# Qgo3.net
KiCad netlist of a schematic drawn in EAGLE
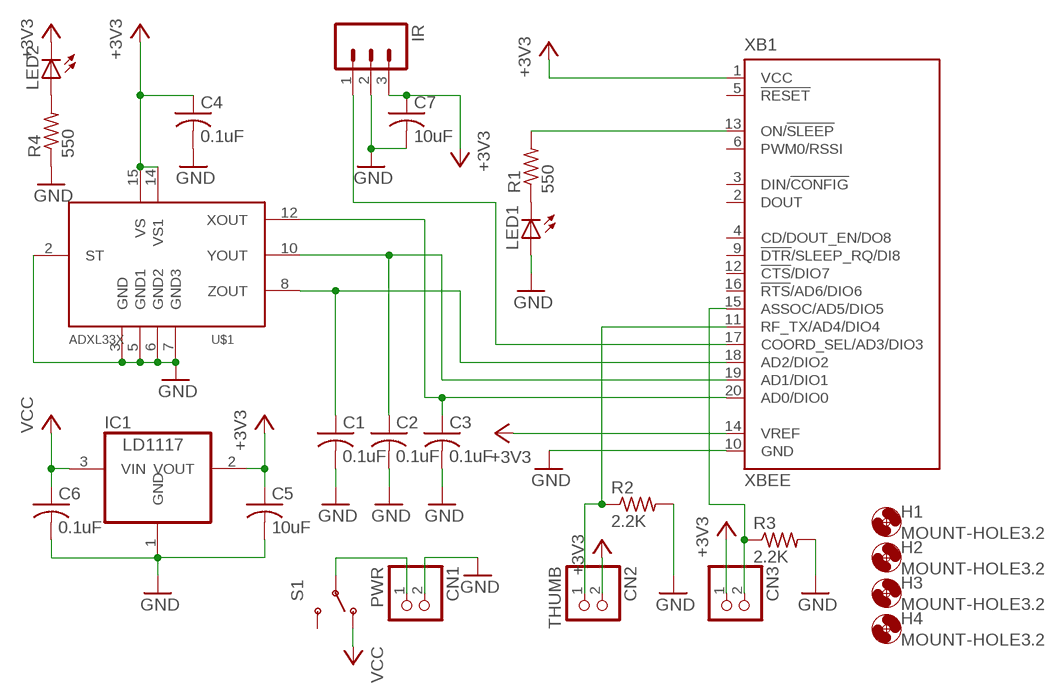
[diagram p0: schematic, sheet 1]

(export (version "E")
  (design (tool "Eeschema 10.0.6"))
  (components
    (comp (ref "C1")
      (value "0.1uF")
      (footprint "eagle-import:C1210")
      (libsource (lib "eagle-import") (part "C-USC1210"))
    )
    (comp (ref "C2")
      (value "0.1uF")
      (footprint "eagle-import:C1210")
      (libsource (lib "eagle-import") (part "C-USC1210"))
    )
    (comp (ref "C3")
      (value "0.1uF")
      (footprint "eagle-import:C1210")
      (libsource (lib "eagle-import") (part "C-USC1210"))
    )
    (comp (ref "C4")
      (value "0.1uF")
      (footprint "eagle-import:C1210")
      (libsource (lib "eagle-import") (part "C-USC1210"))
    )
    (comp (ref "C5")
      (value "10uF")
      (footprint "eagle-import:C1210")
      (libsource (lib "eagle-import") (part "C-USC1210"))
    )
    (comp (ref "C6")
      (value "0.1uF")
      (footprint "eagle-import:C1210")
      (libsource (lib "eagle-import") (part "C-USC1210"))
    )
    (comp (ref "C7")
      (value "10uF")
      (footprint "eagle-import:C1210")
      (libsource (lib "eagle-import") (part "C-USC1210"))
    )
    (comp (ref "CN1")
      (value "PWR")
      (footprint "eagle-import:JST-PH-2-THM-RA")
      (libsource (lib "eagle-import") (part "JST_2PIN-THM-RA"))
    )
    (comp (ref "CN2")
      (value "THUMB")
      (footprint "eagle-import:JST-PH-2-THM-RA")
      (libsource (lib "eagle-import") (part "JST_2PIN-THM-RA"))
    )
    (comp (ref "CN3")
      (value "JST_2PIN-THM-RA")
      (footprint "eagle-import:JST-PH-2-THM-RA")
      (libsource (lib "eagle-import") (part "JST_2PIN-THM-RA"))
    )
    (comp (ref "H1")
      (value "MOUNT-HOLE3.2")
      (footprint "eagle-import:3,2")
      (libsource (lib "eagle-import") (part "MOUNT-HOLE3.2"))
    )
    (comp (ref "H2")
      (value "MOUNT-HOLE3.2")
      (footprint "eagle-import:3,2")
      (libsource (lib "eagle-import") (part "MOUNT-HOLE3.2"))
    )
    (comp (ref "H3")
      (value "MOUNT-HOLE3.2")
      (footprint "eagle-import:3,2")
      (libsource (lib "eagle-import") (part "MOUNT-HOLE3.2"))
    )
    (comp (ref "H4")
      (value "MOUNT-HOLE3.2")
      (footprint "eagle-import:3,2")
      (libsource (lib "eagle-import") (part "MOUNT-HOLE3.2"))
    )
    (comp (ref "IC1")
      (value "LD1117")
      (footprint "eagle-import:SOT223")
      (fields (field (name "MPN") "REG1117"))
      (libsource (lib "eagle-import") (part "LD1117"))
    )
    (comp (ref "IR")
      (value "M03PTH")
      (footprint "eagle-import:1X03")
      (libsource (lib "eagle-import") (part "M03PTH"))
    )
    (comp (ref "LED1")
      (value "LED5MM")
      (footprint "eagle-import:LED5MM")
      (libsource (lib "eagle-import") (part "LED5MM"))
    )
    (comp (ref "LED2")
      (value "LED5MM")
      (footprint "eagle-import:LED5MM")
      (libsource (lib "eagle-import") (part "LED5MM"))
    )
    (comp (ref "R1")
      (value "550")
      (footprint "eagle-import:0207_7")
      (libsource (lib "eagle-import") (part "resistor_R-US_0207/7"))
    )
    (comp (ref "R2")
      (value "2.2K")
      (footprint "eagle-import:0207_7")
      (libsource (lib "eagle-import") (part "R-US_0207/7"))
    )
    (comp (ref "R3")
      (value "2.2K")
      (footprint "eagle-import:0207_7")
      (libsource (lib "eagle-import") (part "R-US_0207/7"))
    )
    (comp (ref "R4")
      (value "550")
      (footprint "eagle-import:0207_7")
      (libsource (lib "eagle-import") (part "resistor_R-US_0207/7"))
    )
    (comp (ref "S1")
      (value "SWITCH-SPDTPTH")
      (footprint "eagle-import:SWITCH-SPDT")
      (libsource (lib "eagle-import") (part "SWITCH-SPDTPTH"))
    )
    (comp (ref "U$1")
      (value "ADXL33X")
      (footprint "eagle-import:16LCSP")
      (libsource (lib "eagle-import") (part "ADXL33X"))
    )
    (comp (ref "XB1")
      (value "XBEE")
      (footprint "eagle-import:XBEE")
      (fields (field (name "MPN") "XBP24-Z7UIT-004"))
      (libsource (lib "eagle-import") (part "XBEE"))
    )
  )
  (nets
    (net (code "1") (name "+3V3") (class "Default")
      (node (ref "C4") (pin "1") (pinfunction "1_1") (pintype "passive"))
      (node (ref "C5") (pin "1") (pinfunction "1_1") (pintype "passive"))
      (node (ref "C7") (pin "1") (pinfunction "1_1") (pintype "passive"))
      (node (ref "CN2") (pin "2") (pinfunction "1_2") (pintype "passive"))
      (node (ref "CN3") (pin "1") (pinfunction "2_1") (pintype "passive"))
      (node (ref "IC1") (pin "2") (pinfunction "VOUT_2") (pintype "power_in"))
      (node (ref "IR") (pin "3") (pinfunction "3_3") (pintype "passive"))
      (node (ref "LED2") (pin "K") (pinfunction "C_K") (pintype "passive"))
      (node (ref "U$1") (pin "14") (pinfunction "VS1_14") (pintype "power_in"))
      (node (ref "U$1") (pin "15") (pinfunction "VS_15") (pintype "power_in"))
      (node (ref "XB1") (pin "1") (pinfunction "VCC_1") (pintype "power_in"))
      (node (ref "XB1") (pin "14") (pinfunction "VREF_14") (pintype "input"))
    )
    (net (code "2") (name "GND") (class "Default")
      (node (ref "C1") (pin "2") (pinfunction "2_2") (pintype "passive"))
      (node (ref "C2") (pin "2") (pinfunction "2_2") (pintype "passive"))
      (node (ref "C3") (pin "2") (pinfunction "2_2") (pintype "passive"))
      (node (ref "C4") (pin "2") (pinfunction "2_2") (pintype "passive"))
      (node (ref "C5") (pin "2") (pinfunction "2_2") (pintype "passive"))
      (node (ref "C6") (pin "2") (pinfunction "2_2") (pintype "passive"))
      (node (ref "C7") (pin "2") (pinfunction "2_2") (pintype "passive"))
      (node (ref "CN1") (pin "2") (pinfunction "1_2") (pintype "passive"))
      (node (ref "IC1") (pin "1") (pinfunction "GND_1") (pintype "power_in"))
      (node (ref "IR") (pin "2") (pinfunction "2_2") (pintype "passive"))
      (node (ref "LED1") (pin "A") (pinfunction "A_A") (pintype "passive"))
      (node (ref "R2") (pin "2") (pinfunction "2_2") (pintype "passive"))
      (node (ref "R3") (pin "2") (pinfunction "2_2") (pintype "passive"))
      (node (ref "R4") (pin "1") (pinfunction "1_1") (pintype "passive"))
      (node (ref "U$1") (pin "2") (pinfunction "ST_2") (pintype "input"))
      (node (ref "U$1") (pin "3") (pinfunction "GND_3") (pintype "power_in"))
      (node (ref "U$1") (pin "5") (pinfunction "GND1_5") (pintype "power_in"))
      (node (ref "U$1") (pin "6") (pinfunction "GND2_6") (pintype "power_in"))
      (node (ref "U$1") (pin "7") (pinfunction "GND3_7") (pintype "power_in"))
      (node (ref "XB1") (pin "10") (pinfunction "GND_10") (pintype "power_in"))
    )
    (net (code "3") (name "Net-(CN1-2)") (class "Default")
      (node (ref "CN1") (pin "1") (pinfunction "2_1") (pintype "passive"))
      (node (ref "S1") (pin "2") (pinfunction "P_2") (pintype "passive"))
    )
    (net (code "4") (name "Net-(CN2-2)") (class "Default")
      (node (ref "CN2") (pin "1") (pinfunction "2_1") (pintype "passive"))
      (node (ref "R2") (pin "1") (pinfunction "1_1") (pintype "passive"))
      (node (ref "XB1") (pin "11") (pinfunction "RF_TX/AD4/DIO4_11") (pintype "bidirectional"))
    )
    (net (code "5") (name "Net-(CN3-1)") (class "Default")
      (node (ref "CN3") (pin "2") (pinfunction "1_2") (pintype "passive"))
      (node (ref "R3") (pin "1") (pinfunction "1_1") (pintype "passive"))
      (node (ref "XB1") (pin "15") (pinfunction "ASSOC/AD5/DIO5_15") (pintype "bidirectional"))
    )
    (net (code "6") (name "Net-(LED1-C)") (class "Default")
      (node (ref "LED1") (pin "K") (pinfunction "C_K") (pintype "passive"))
      (node (ref "R1") (pin "1") (pinfunction "1_1") (pintype "passive"))
    )
    (net (code "7") (name "Net-(LED2-PadA)") (class "Default")
      (node (ref "LED2") (pin "A") (pinfunction "A_A") (pintype "passive"))
      (node (ref "R4") (pin "2") (pinfunction "2_2") (pintype "passive"))
    )
    (net (code "8") (name "Net-(U$1-XOUT)") (class "Default")
      (node (ref "C3") (pin "1") (pinfunction "1_1") (pintype "passive"))
      (node (ref "U$1") (pin "12") (pinfunction "XOUT_12") (pintype "output"))
      (node (ref "XB1") (pin "20") (pinfunction "AD0/DIO0_20") (pintype "bidirectional"))
    )
    (net (code "9") (name "Net-(U$1-YOUT)") (class "Default")
      (node (ref "C2") (pin "1") (pinfunction "1_1") (pintype "passive"))
      (node (ref "U$1") (pin "10") (pinfunction "YOUT_10") (pintype "output"))
      (node (ref "XB1") (pin "19") (pinfunction "AD1/DIO1_19") (pintype "bidirectional"))
    )
    (net (code "10") (name "Net-(U$1-ZOUT)") (class "Default")
      (node (ref "C1") (pin "1") (pinfunction "1_1") (pintype "passive"))
      (node (ref "U$1") (pin "8") (pinfunction "ZOUT_8") (pintype "output"))
      (node (ref "XB1") (pin "18") (pinfunction "AD2/DIO2_18") (pintype "bidirectional"))
    )
    (net (code "11") (name "Net-(XB1-COORD_SEL{slash}AD3{slash}DIO3)") (class "Default")
      (node (ref "IR") (pin "1") (pinfunction "1_1") (pintype "passive"))
      (node (ref "XB1") (pin "17") (pinfunction "COORD_SEL/AD3/DIO3_17") (pintype "bidirectional"))
    )
    (net (code "12") (name "Net-(XB1-ON{slash}~{SLEEP})") (class "Default")
      (node (ref "R1") (pin "2") (pinfunction "2_2") (pintype "passive"))
      (node (ref "XB1") (pin "13") (pinfunction "ON/~{SLEEP}_13") (pintype "output"))
    )
    (net (code "13") (name "VCC") (class "Default")
      (node (ref "C6") (pin "1") (pinfunction "1_1") (pintype "passive"))
      (node (ref "IC1") (pin "3") (pinfunction "VIN_3") (pintype "input"))
      (node (ref "S1") (pin "1") (pinfunction "O_1") (pintype "passive"))
    )
    (net (code "14") (name "unconnected-(S1-S-Pad3)") (class "Default")
      (node (ref "S1") (pin "3") (pinfunction "S_3") (pintype "passive"))
    )
    (net (code "15") (name "unconnected-(XB1-CD{slash}DOUT_EN{slash}DO8-Pad4)") (class "Default")
      (node (ref "XB1") (pin "4") (pinfunction "CD/DOUT_EN/DO8_4") (pintype "output"))
    )
    (net (code "16") (name "unconnected-(XB1-DIN{slash}~{CONFIG}-Pad3)") (class "Default")
      (node (ref "XB1") (pin "3") (pinfunction "DIN/~{CONFIG}_3") (pintype "input"))
    )
    (net (code "17") (name "unconnected-(XB1-DOUT-Pad2)") (class "Default")
      (node (ref "XB1") (pin "2") (pinfunction "DOUT_2") (pintype "output"))
    )
    (net (code "18") (name "unconnected-(XB1-PWM0{slash}RSSI-Pad6)") (class "Default")
      (node (ref "XB1") (pin "6") (pinfunction "PWM0/RSSI_6") (pintype "output"))
    )
    (net (code "19") (name "unconnected-(XB1-~{CTS}{slash}DIO7-Pad12)") (class "Default")
      (node (ref "XB1") (pin "12") (pinfunction "~{CTS}/DIO7_12") (pintype "bidirectional"))
    )
    (net (code "20") (name "unconnected-(XB1-~{DTR}{slash}SLEEP_RQ{slash}DI8-Pad9)") (class "Default")
      (node (ref "XB1") (pin "9") (pinfunction "~{DTR}/SLEEP_RQ/DI8_9") (pintype "bidirectional"))
    )
    (net (code "21") (name "unconnected-(XB1-~{RESET}-Pad5)") (class "Default")
      (node (ref "XB1") (pin "5") (pinfunction "~{RESET}_5") (pintype "input"))
    )
    (net (code "22") (name "unconnected-(XB1-~{RTS}{slash}AD6{slash}DIO6-Pad16)") (class "Default")
      (node (ref "XB1") (pin "16") (pinfunction "~{RTS}/AD6/DIO6_16") (pintype "bidirectional"))
    )
  )
)
